# sensors_in.net
KiCad netlist of a schematic drawn in Altium Designer
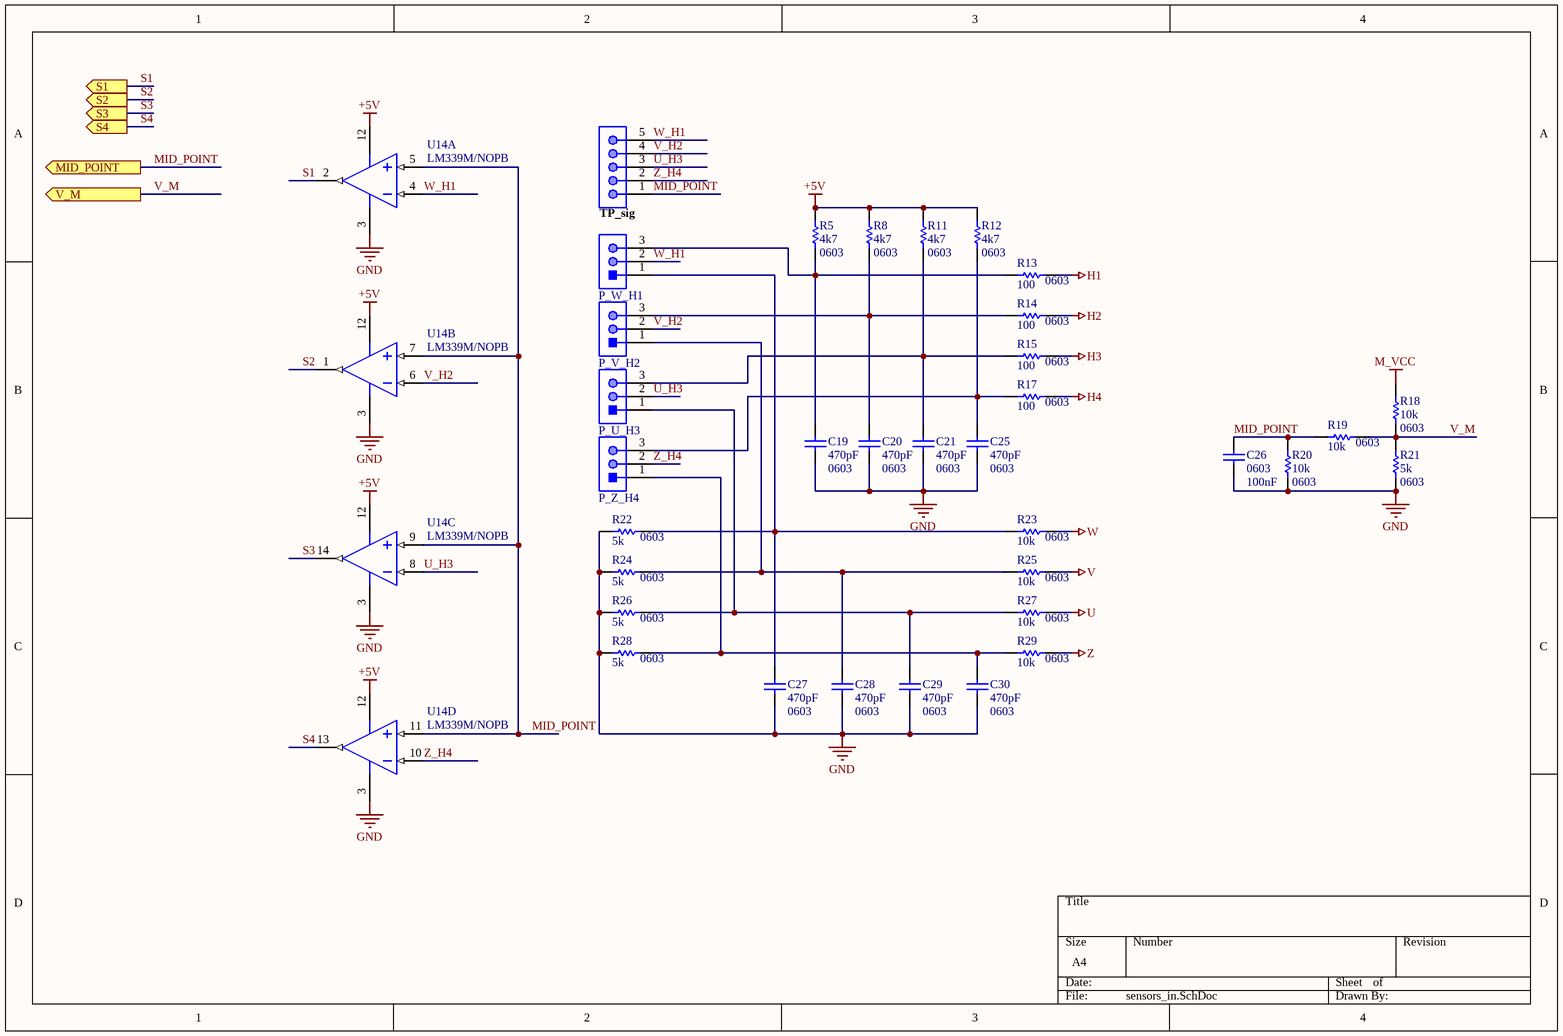
[diagram p0: sensors_in.SchDoc]

(export (version "E")
  (design (tool "Eeschema 10.0.6"))
  (components
    (comp (ref "C19")
      (value "470pF")
      (footprint "CAPC0603(1608)100_M")
      (description "CAP 470pF 25V ±5% 0603 (1608 Metric) Thickness 1mm SMD")
      (fields
        (field (name "TOLERANCE") "Â±5%")
        (field (name "CASE-EIA") "0603")
        (field (name "Comment") "CAP 470pF 25V 0603(1608)")
      )
      (libsource (lib "Altium Content Vault") (part "CAP"))
    )
    (comp (ref "C20")
      (value "470pF")
      (footprint "CAPC0603(1608)100_M")
      (description "CAP 470pF 25V ±5% 0603 (1608 Metric) Thickness 1mm SMD")
      (fields
        (field (name "TOLERANCE") "Â±5%")
        (field (name "CASE-EIA") "0603")
        (field (name "Comment") "CAP 470pF 25V 0603(1608)")
      )
      (libsource (lib "Altium Content Vault") (part "CAP"))
    )
    (comp (ref "C21")
      (value "470pF")
      (footprint "CAPC0603(1608)100_M")
      (description "CAP 470pF 25V ±5% 0603 (1608 Metric) Thickness 1mm SMD")
      (fields
        (field (name "TOLERANCE") "Â±5%")
        (field (name "CASE-EIA") "0603")
        (field (name "Comment") "CAP 470pF 25V 0603(1608)")
      )
      (libsource (lib "Altium Content Vault") (part "CAP"))
    )
    (comp (ref "C25")
      (value "470pF")
      (footprint "CAPC0603(1608)100_M")
      (description "CAP 470pF 25V ±5% 0603 (1608 Metric) Thickness 1mm SMD")
      (fields
        (field (name "TOLERANCE") "Â±5%")
        (field (name "CASE-EIA") "0603")
        (field (name "Comment") "CAP 470pF 25V 0603(1608)")
      )
      (libsource (lib "Altium Content Vault") (part "CAP"))
    )
    (comp (ref "C26")
      (value "GRM188R71H104KA93D")
      (footprint "CAPC1608X90X35ML10T15")
      (description "Chip Capacitor, 0.1 uF, +/- 10%, 50 V, -55 to 125 degC, 0603 (1608 Metric), RoHS, Tape and Reel")
      (fields
        (field (name "TOLERANCE") "10%")
        (field (name "CASE CODE (IMPERIAL)") "0603")
        (field (name "CAPACITANCE") "100nF")
        (field (name "VOLTAGE") "50V")
      )
      (libsource (lib "Altium Content Vault") (part "CAP-NP-2"))
    )
    (comp (ref "C27")
      (value "470pF")
      (footprint "CAPC0603(1608)100_M")
      (description "CAP 470pF 25V ±5% 0603 (1608 Metric) Thickness 1mm SMD")
      (fields
        (field (name "TOLERANCE") "Â±5%")
        (field (name "CASE-EIA") "0603")
        (field (name "Comment") "CAP 470pF 25V 0603(1608)")
      )
      (libsource (lib "Altium Content Vault") (part "CAP"))
    )
    (comp (ref "C28")
      (value "470pF")
      (footprint "CAPC0603(1608)100_M")
      (description "CAP 470pF 25V ±5% 0603 (1608 Metric) Thickness 1mm SMD")
      (fields
        (field (name "TOLERANCE") "Â±5%")
        (field (name "CASE-EIA") "0603")
        (field (name "Comment") "CAP 470pF 25V 0603(1608)")
      )
      (libsource (lib "Altium Content Vault") (part "CAP"))
    )
    (comp (ref "C29")
      (value "470pF")
      (footprint "CAPC0603(1608)100_M")
      (description "CAP 470pF 25V ±5% 0603 (1608 Metric) Thickness 1mm SMD")
      (fields
        (field (name "TOLERANCE") "Â±5%")
        (field (name "CASE-EIA") "0603")
        (field (name "Comment") "CAP 470pF 25V 0603(1608)")
      )
      (libsource (lib "Altium Content Vault") (part "CAP"))
    )
    (comp (ref "C30")
      (value "470pF")
      (footprint "CAPC0603(1608)100_M")
      (description "CAP 470pF 25V ±5% 0603 (1608 Metric) Thickness 1mm SMD")
      (fields
        (field (name "TOLERANCE") "Â±5%")
        (field (name "CASE-EIA") "0603")
        (field (name "Comment") "CAP 470pF 25V 0603(1608)")
      )
      (libsource (lib "Altium Content Vault") (part "CAP"))
    )
    (comp (ref "P_U_H3")
      (value "61300311121")
      (footprint "61300311121")
      (description "THT Vertical Pin Header WR-PHD, Pitch 2.54 mm, Single Row, 3 pins")
      (fields (field (name "MANUFACTURER") "Wurth Elektronik") (field (name "PUBLISHER") "WurthElektronik"))
      (libsource (lib "Altium Content Vault") (part "WE-CN-1P-M-R3"))
    )
    (comp (ref "P_V_H2")
      (value "61300311121")
      (footprint "61300311121")
      (description "THT Vertical Pin Header WR-PHD, Pitch 2.54 mm, Single Row, 3 pins")
      (fields (field (name "MANUFACTURER") "Wurth Elektronik") (field (name "PUBLISHER") "WurthElektronik"))
      (libsource (lib "Altium Content Vault") (part "WE-CN-1P-M-R3"))
    )
    (comp (ref "P_W_H1")
      (value "61300311121")
      (footprint "61300311121")
      (description "THT Vertical Pin Header WR-PHD, Pitch 2.54 mm, Single Row, 3 pins")
      (fields (field (name "MANUFACTURER") "Wurth Elektronik") (field (name "PUBLISHER") "WurthElektronik"))
      (libsource (lib "Altium Content Vault") (part "WE-CN-1P-M-R3"))
    )
    (comp (ref "P_Z_H4")
      (value "61300311121")
      (footprint "61300311121")
      (description "THT Vertical Pin Header WR-PHD, Pitch 2.54 mm, Single Row, 3 pins")
      (fields (field (name "MANUFACTURER") "Wurth Elektronik") (field (name "PUBLISHER") "WurthElektronik"))
      (libsource (lib "Altium Content Vault") (part "WE-CN-1P-M-R3"))
    )
    (comp (ref "R5")
      (value "RMCF0603FT10K0")
      (footprint "RESC1608X55X30ML15T20")
      (description "Chip Resistor, 10 KOhm, +/- 1%, 0.1 W, -55 to 155 degC, 0603 (1608 Metric), RoHS, Tape and Reel")
      (fields
        (field (name "RESISTANCE (OHMS)") "4k7")
        (field (name "TOLERANCE") "±1%")
        (field (name "PACKAGE REFERENCE") "0603")
        (field (name "MANUFACTURER") "Stackpole-Electronics-Inc.")
      )
      (libsource (lib "Altium Content Vault") (part "RES-2"))
    )
    (comp (ref "R8")
      (value "RMCF0603FT10K0")
      (footprint "RESC1608X55X30ML15T20")
      (description "Chip Resistor, 10 KOhm, +/- 1%, 0.1 W, -55 to 155 degC, 0603 (1608 Metric), RoHS, Tape and Reel")
      (fields
        (field (name "RESISTANCE (OHMS)") "4k7")
        (field (name "TOLERANCE") "±1%")
        (field (name "PACKAGE REFERENCE") "0603")
        (field (name "MANUFACTURER") "Stackpole-Electronics-Inc.")
      )
      (libsource (lib "Altium Content Vault") (part "RES-2"))
    )
    (comp (ref "R11")
      (value "RMCF0603FT10K0")
      (footprint "RESC1608X55X30ML15T20")
      (description "Chip Resistor, 10 KOhm, +/- 1%, 0.1 W, -55 to 155 degC, 0603 (1608 Metric), RoHS, Tape and Reel")
      (fields
        (field (name "RESISTANCE (OHMS)") "4k7")
        (field (name "TOLERANCE") "±1%")
        (field (name "PACKAGE REFERENCE") "0603")
        (field (name "MANUFACTURER") "Stackpole-Electronics-Inc.")
      )
      (libsource (lib "Altium Content Vault") (part "RES-2"))
    )
    (comp (ref "R12")
      (value "RMCF0603FT10K0")
      (footprint "RESC1608X55X30ML15T20")
      (description "Chip Resistor, 10 KOhm, +/- 1%, 0.1 W, -55 to 155 degC, 0603 (1608 Metric), RoHS, Tape and Reel")
      (fields
        (field (name "RESISTANCE (OHMS)") "4k7")
        (field (name "TOLERANCE") "±1%")
        (field (name "PACKAGE REFERENCE") "0603")
        (field (name "MANUFACTURER") "Stackpole-Electronics-Inc.")
      )
      (libsource (lib "Altium Content Vault") (part "RES-2"))
    )
    (comp (ref "R13")
      (value "RMCF0603FT10K0")
      (footprint "RESC1608X55X30ML15T20")
      (description "Chip Resistor, 10 KOhm, +/- 1%, 0.1 W, -55 to 155 degC, 0603 (1608 Metric), RoHS, Tape and Reel")
      (fields
        (field (name "RESISTANCE (OHMS)") "100")
        (field (name "TOLERANCE") "±1%")
        (field (name "PACKAGE REFERENCE") "0603")
        (field (name "MANUFACTURER") "Stackpole-Electronics-Inc.")
      )
      (libsource (lib "Altium Content Vault") (part "RES-2"))
    )
    (comp (ref "R14")
      (value "RMCF0603FT10K0")
      (footprint "RESC1608X55X30ML15T20")
      (description "Chip Resistor, 10 KOhm, +/- 1%, 0.1 W, -55 to 155 degC, 0603 (1608 Metric), RoHS, Tape and Reel")
      (fields
        (field (name "RESISTANCE (OHMS)") "100")
        (field (name "TOLERANCE") "±1%")
        (field (name "PACKAGE REFERENCE") "0603")
        (field (name "MANUFACTURER") "Stackpole-Electronics-Inc.")
      )
      (libsource (lib "Altium Content Vault") (part "RES-2"))
    )
    (comp (ref "R15")
      (value "RMCF0603FT10K0")
      (footprint "RESC1608X55X30ML15T20")
      (description "Chip Resistor, 10 KOhm, +/- 1%, 0.1 W, -55 to 155 degC, 0603 (1608 Metric), RoHS, Tape and Reel")
      (fields
        (field (name "RESISTANCE (OHMS)") "100")
        (field (name "TOLERANCE") "±1%")
        (field (name "PACKAGE REFERENCE") "0603")
        (field (name "MANUFACTURER") "Stackpole-Electronics-Inc.")
      )
      (libsource (lib "Altium Content Vault") (part "RES-2"))
    )
    (comp (ref "R17")
      (value "RMCF0603FT10K0")
      (footprint "RESC1608X55X30ML15T20")
      (description "Chip Resistor, 10 KOhm, +/- 1%, 0.1 W, -55 to 155 degC, 0603 (1608 Metric), RoHS, Tape and Reel")
      (fields
        (field (name "RESISTANCE (OHMS)") "100")
        (field (name "TOLERANCE") "±1%")
        (field (name "PACKAGE REFERENCE") "0603")
        (field (name "MANUFACTURER") "Stackpole-Electronics-Inc.")
      )
      (libsource (lib "Altium Content Vault") (part "RES-2"))
    )
    (comp (ref "R18")
      (value "RMCF0603FT10K0")
      (footprint "RESC1608X55X30ML15T20")
      (description "Chip Resistor, 10 KOhm, +/- 1%, 0.1 W, -55 to 155 degC, 0603 (1608 Metric), RoHS, Tape and Reel")
      (fields
        (field (name "RESISTANCE (OHMS)") "10k")
        (field (name "TOLERANCE") "±1%")
        (field (name "PACKAGE REFERENCE") "0603")
        (field (name "MANUFACTURER") "Stackpole-Electronics-Inc.")
      )
      (libsource (lib "Altium Content Vault") (part "RES-2"))
    )
    (comp (ref "R19")
      (value "RMCF0603FT10K0")
      (footprint "RESC1608X55X30ML15T20")
      (description "Chip Resistor, 10 KOhm, +/- 1%, 0.1 W, -55 to 155 degC, 0603 (1608 Metric), RoHS, Tape and Reel")
      (fields
        (field (name "RESISTANCE (OHMS)") "10k")
        (field (name "TOLERANCE") "±1%")
        (field (name "PACKAGE REFERENCE") "0603")
        (field (name "MANUFACTURER") "Stackpole-Electronics-Inc.")
      )
      (libsource (lib "Altium Content Vault") (part "RES-2"))
    )
    (comp (ref "R20")
      (value "RMCF0603FT10K0")
      (footprint "RESC1608X55X30ML15T20")
      (description "Chip Resistor, 10 KOhm, +/- 1%, 0.1 W, -55 to 155 degC, 0603 (1608 Metric), RoHS, Tape and Reel")
      (fields
        (field (name "RESISTANCE (OHMS)") "10k")
        (field (name "TOLERANCE") "±1%")
        (field (name "PACKAGE REFERENCE") "0603")
        (field (name "MANUFACTURER") "Stackpole-Electronics-Inc.")
      )
      (libsource (lib "Altium Content Vault") (part "RES-2"))
    )
    (comp (ref "R21")
      (value "RMCF0603FT10K0")
      (footprint "RESC1608X55X30ML15T20")
      (description "Chip Resistor, 10 KOhm, +/- 1%, 0.1 W, -55 to 155 degC, 0603 (1608 Metric), RoHS, Tape and Reel")
      (fields
        (field (name "RESISTANCE (OHMS)") "5k")
        (field (name "TOLERANCE") "±1%")
        (field (name "PACKAGE REFERENCE") "0603")
        (field (name "MANUFACTURER") "Stackpole-Electronics-Inc.")
      )
      (libsource (lib "Altium Content Vault") (part "RES-2"))
    )
    (comp (ref "R22")
      (value "RMCF0603FT10K0")
      (footprint "RESC1608X55X30ML15T20")
      (description "Chip Resistor, 10 KOhm, +/- 1%, 0.1 W, -55 to 155 degC, 0603 (1608 Metric), RoHS, Tape and Reel")
      (fields
        (field (name "RESISTANCE (OHMS)") "5k")
        (field (name "TOLERANCE") "±1%")
        (field (name "PACKAGE REFERENCE") "0603")
        (field (name "MANUFACTURER") "Stackpole-Electronics-Inc.")
      )
      (libsource (lib "Altium Content Vault") (part "RES-2"))
    )
    (comp (ref "R23")
      (value "RMCF0603FT10K0")
      (footprint "RESC1608X55X30ML15T20")
      (description "Chip Resistor, 10 KOhm, +/- 1%, 0.1 W, -55 to 155 degC, 0603 (1608 Metric), RoHS, Tape and Reel")
      (fields
        (field (name "RESISTANCE (OHMS)") "10k")
        (field (name "TOLERANCE") "±1%")
        (field (name "PACKAGE REFERENCE") "0603")
        (field (name "MANUFACTURER") "Stackpole-Electronics-Inc.")
      )
      (libsource (lib "Altium Content Vault") (part "RES-2"))
    )
    (comp (ref "R24")
      (value "RMCF0603FT10K0")
      (footprint "RESC1608X55X30ML15T20")
      (description "Chip Resistor, 10 KOhm, +/- 1%, 0.1 W, -55 to 155 degC, 0603 (1608 Metric), RoHS, Tape and Reel")
      (fields
        (field (name "RESISTANCE (OHMS)") "5k")
        (field (name "TOLERANCE") "±1%")
        (field (name "PACKAGE REFERENCE") "0603")
        (field (name "MANUFACTURER") "Stackpole-Electronics-Inc.")
      )
      (libsource (lib "Altium Content Vault") (part "RES-2"))
    )
    (comp (ref "R25")
      (value "RMCF0603FT10K0")
      (footprint "RESC1608X55X30ML15T20")
      (description "Chip Resistor, 10 KOhm, +/- 1%, 0.1 W, -55 to 155 degC, 0603 (1608 Metric), RoHS, Tape and Reel")
      (fields
        (field (name "RESISTANCE (OHMS)") "10k")
        (field (name "TOLERANCE") "±1%")
        (field (name "PACKAGE REFERENCE") "0603")
        (field (name "MANUFACTURER") "Stackpole-Electronics-Inc.")
      )
      (libsource (lib "Altium Content Vault") (part "RES-2"))
    )
    (comp (ref "R26")
      (value "RMCF0603FT10K0")
      (footprint "RESC1608X55X30ML15T20")
      (description "Chip Resistor, 10 KOhm, +/- 1%, 0.1 W, -55 to 155 degC, 0603 (1608 Metric), RoHS, Tape and Reel")
      (fields
        (field (name "RESISTANCE (OHMS)") "5k")
        (field (name "TOLERANCE") "±1%")
        (field (name "PACKAGE REFERENCE") "0603")
        (field (name "MANUFACTURER") "Stackpole-Electronics-Inc.")
      )
      (libsource (lib "Altium Content Vault") (part "RES-2"))
    )
    (comp (ref "R27")
      (value "RMCF0603FT10K0")
      (footprint "RESC1608X55X30ML15T20")
      (description "Chip Resistor, 10 KOhm, +/- 1%, 0.1 W, -55 to 155 degC, 0603 (1608 Metric), RoHS, Tape and Reel")
      (fields
        (field (name "RESISTANCE (OHMS)") "10k")
        (field (name "TOLERANCE") "±1%")
        (field (name "PACKAGE REFERENCE") "0603")
        (field (name "MANUFACTURER") "Stackpole-Electronics-Inc.")
      )
      (libsource (lib "Altium Content Vault") (part "RES-2"))
    )
    (comp (ref "R28")
      (value "RMCF0603FT10K0")
      (footprint "RESC1608X55X30ML15T20")
      (description "Chip Resistor, 10 KOhm, +/- 1%, 0.1 W, -55 to 155 degC, 0603 (1608 Metric), RoHS, Tape and Reel")
      (fields
        (field (name "RESISTANCE (OHMS)") "5k")
        (field (name "TOLERANCE") "±1%")
        (field (name "PACKAGE REFERENCE") "0603")
        (field (name "MANUFACTURER") "Stackpole-Electronics-Inc.")
      )
      (libsource (lib "Altium Content Vault") (part "RES-2"))
    )
    (comp (ref "R29")
      (value "RMCF0603FT10K0")
      (footprint "RESC1608X55X30ML15T20")
      (description "Chip Resistor, 10 KOhm, +/- 1%, 0.1 W, -55 to 155 degC, 0603 (1608 Metric), RoHS, Tape and Reel")
      (fields
        (field (name "RESISTANCE (OHMS)") "10k")
        (field (name "TOLERANCE") "±1%")
        (field (name "PACKAGE REFERENCE") "0603")
        (field (name "MANUFACTURER") "Stackpole-Electronics-Inc.")
      )
      (libsource (lib "Altium Content Vault") (part "RES-2"))
    )
    (comp (ref "TP_sig")
      (value "PH2541-5-SPGRH-6-3")
      (footprint "PH2541-5-SPGRH-6-3_V")
      (description "Male Header, Pitch 2.54mm, 5x1 Position, Mated Height 6mm, Tail Length 3mm")
      (libsource (lib "Altium Content Vault") (part "PCE-HDR-1P-M-R5"))
    )
    (comp (ref "U14")
      (value "LM339M/NOPB")
      (footprint "D0014A_L")
      (description "Low Power Low Offset Voltage Quad Comparator, 14-pin Narrow SOIC, Pb-Free")
      (fields (field (name "MANUFACTURER") "Texas Instruments"))
      (libsource (lib "Altium Content Vault") (part "AN-COMP-LM139-14"))
    )
  )
  (nets
    (net (code "1") (name "+5V") (class "Default")
      (node (ref "R11") (pin "2") (pinfunction "2_2") (pintype "passive"))
      (node (ref "R12") (pin "2") (pinfunction "2_2") (pintype "passive"))
      (node (ref "R5") (pin "2") (pinfunction "2_2") (pintype "passive"))
      (node (ref "R8") (pin "2") (pinfunction "2_2") (pintype "passive"))
      (node (ref "U14") (pin "12") (pinfunction "GND_12") (pintype "power_in"))
    )
    (net (code "2") (name "/MID_POINT") (class "Default")
      (node (ref "C26") (pin "2") (pinfunction "2_2") (pintype "passive"))
      (node (ref "R19") (pin "1") (pinfunction "1_1") (pintype "passive"))
      (node (ref "R20") (pin "2") (pinfunction "2_2") (pintype "passive"))
      (node (ref "TP_sig") (pin "1") (pinfunction "1_1") (pintype "passive"))
      (node (ref "U14") (pin "11") (pinfunction "IN4+_11") (pintype "input"))
      (node (ref "U14") (pin "5") (pinfunction "IN1+_5") (pintype "input"))
      (node (ref "U14") (pin "7") (pinfunction "IN2+_7") (pintype "input"))
      (node (ref "U14") (pin "9") (pinfunction "IN3+_9") (pintype "input"))
    )
    (net (code "3") (name "/S1") (class "Default")
      (node (ref "U14") (pin "2") (pinfunction "OUT1_2") (pintype "output"))
    )
    (net (code "4") (name "/S2") (class "Default")
      (node (ref "U14") (pin "1") (pinfunction "OUT2_1") (pintype "output"))
    )
    (net (code "5") (name "/S3") (class "Default")
      (node (ref "U14") (pin "14") (pinfunction "OUT3_14") (pintype "output"))
    )
    (net (code "6") (name "/S4") (class "Default")
      (node (ref "U14") (pin "13") (pinfunction "OUT4_13") (pintype "output"))
    )
    (net (code "7") (name "/U_H3") (class "Default")
      (node (ref "P_U_H3") (pin "2") (pinfunction "2_2") (pintype "passive"))
      (node (ref "TP_sig") (pin "3") (pinfunction "3_3") (pintype "passive"))
      (node (ref "U14") (pin "8") (pinfunction "IN3-_8") (pintype "input"))
    )
    (net (code "8") (name "/V_H2") (class "Default")
      (node (ref "P_V_H2") (pin "2") (pinfunction "2_2") (pintype "passive"))
      (node (ref "TP_sig") (pin "4") (pinfunction "4_4") (pintype "passive"))
      (node (ref "U14") (pin "6") (pinfunction "IN2-_6") (pintype "input"))
    )
    (net (code "9") (name "/V_M") (class "Default")
      (node (ref "R18") (pin "1") (pinfunction "1_1") (pintype "passive"))
      (node (ref "R19") (pin "2") (pinfunction "2_2") (pintype "passive"))
      (node (ref "R21") (pin "2") (pinfunction "2_2") (pintype "passive"))
    )
    (net (code "10") (name "/W_H1") (class "Default")
      (node (ref "P_W_H1") (pin "2") (pinfunction "2_2") (pintype "passive"))
      (node (ref "TP_sig") (pin "5") (pinfunction "5_5") (pintype "passive"))
      (node (ref "U14") (pin "4") (pinfunction "IN1-_4") (pintype "input"))
    )
    (net (code "11") (name "/Z_H4") (class "Default")
      (node (ref "P_Z_H4") (pin "2") (pinfunction "2_2") (pintype "passive"))
      (node (ref "TP_sig") (pin "2") (pinfunction "2_2") (pintype "passive"))
      (node (ref "U14") (pin "10") (pinfunction "IN4-_10") (pintype "input"))
    )
    (net (code "12") (name "GND") (class "Default")
      (node (ref "C19") (pin "1") (pinfunction "1_1") (pintype "passive"))
      (node (ref "C20") (pin "1") (pinfunction "1_1") (pintype "passive"))
      (node (ref "C21") (pin "1") (pinfunction "1_1") (pintype "passive"))
      (node (ref "C25") (pin "1") (pinfunction "1_1") (pintype "passive"))
      (node (ref "C26") (pin "1") (pinfunction "1_1") (pintype "passive"))
      (node (ref "C27") (pin "1") (pinfunction "1_1") (pintype "passive"))
      (node (ref "C28") (pin "1") (pinfunction "1_1") (pintype "passive"))
      (node (ref "C29") (pin "1") (pinfunction "1_1") (pintype "passive"))
      (node (ref "C30") (pin "1") (pinfunction "1_1") (pintype "passive"))
      (node (ref "R20") (pin "1") (pinfunction "1_1") (pintype "passive"))
      (node (ref "R21") (pin "1") (pinfunction "1_1") (pintype "passive"))
      (node (ref "R22") (pin "1") (pinfunction "1_1") (pintype "passive"))
      (node (ref "R24") (pin "1") (pinfunction "1_1") (pintype "passive"))
      (node (ref "R26") (pin "1") (pinfunction "1_1") (pintype "passive"))
      (node (ref "R28") (pin "1") (pinfunction "1_1") (pintype "passive"))
      (node (ref "U14") (pin "3") (pinfunction "V+_3") (pintype "power_in"))
    )
    (net (code "13") (name "H1") (class "Default")
      (node (ref "R13") (pin "2") (pinfunction "2_2") (pintype "passive"))
    )
    (net (code "14") (name "H2") (class "Default")
      (node (ref "R14") (pin "2") (pinfunction "2_2") (pintype "passive"))
    )
    (net (code "15") (name "H3") (class "Default")
      (node (ref "R15") (pin "2") (pinfunction "2_2") (pintype "passive"))
    )
    (net (code "16") (name "H4") (class "Default")
      (node (ref "R17") (pin "2") (pinfunction "2_2") (pintype "passive"))
    )
    (net (code "17") (name "M_VCC") (class "Default")
      (node (ref "R18") (pin "2") (pinfunction "2_2") (pintype "passive"))
    )
    (net (code "18") (name "Net-(C19-Pad2)") (class "Default")
      (node (ref "C19") (pin "2") (pinfunction "2_2") (pintype "passive"))
      (node (ref "P_W_H1") (pin "3") (pinfunction "3_3") (pintype "passive"))
      (node (ref "R13") (pin "1") (pinfunction "1_1") (pintype "passive"))
      (node (ref "R5") (pin "1") (pinfunction "1_1") (pintype "passive"))
    )
    (net (code "19") (name "Net-(C20-Pad2)") (class "Default")
      (node (ref "C20") (pin "2") (pinfunction "2_2") (pintype "passive"))
      (node (ref "P_V_H2") (pin "3") (pinfunction "3_3") (pintype "passive"))
      (node (ref "R14") (pin "1") (pinfunction "1_1") (pintype "passive"))
      (node (ref "R8") (pin "1") (pinfunction "1_1") (pintype "passive"))
    )
    (net (code "20") (name "Net-(C21-Pad2)") (class "Default")
      (node (ref "C21") (pin "2") (pinfunction "2_2") (pintype "passive"))
      (node (ref "P_U_H3") (pin "3") (pinfunction "3_3") (pintype "passive"))
      (node (ref "R11") (pin "1") (pinfunction "1_1") (pintype "passive"))
      (node (ref "R15") (pin "1") (pinfunction "1_1") (pintype "passive"))
    )
    (net (code "21") (name "Net-(C25-Pad2)") (class "Default")
      (node (ref "C25") (pin "2") (pinfunction "2_2") (pintype "passive"))
      (node (ref "P_Z_H4") (pin "3") (pinfunction "3_3") (pintype "passive"))
      (node (ref "R12") (pin "1") (pinfunction "1_1") (pintype "passive"))
      (node (ref "R17") (pin "1") (pinfunction "1_1") (pintype "passive"))
    )
    (net (code "22") (name "Net-(C27-Pad2)") (class "Default")
      (node (ref "C27") (pin "2") (pinfunction "2_2") (pintype "passive"))
      (node (ref "P_W_H1") (pin "1") (pinfunction "1_1") (pintype "passive"))
      (node (ref "R22") (pin "2") (pinfunction "2_2") (pintype "passive"))
      (node (ref "R23") (pin "1") (pinfunction "1_1") (pintype "passive"))
    )
    (net (code "23") (name "Net-(C28-Pad2)") (class "Default")
      (node (ref "C28") (pin "2") (pinfunction "2_2") (pintype "passive"))
      (node (ref "P_V_H2") (pin "1") (pinfunction "1_1") (pintype "passive"))
      (node (ref "R24") (pin "2") (pinfunction "2_2") (pintype "passive"))
      (node (ref "R25") (pin "1") (pinfunction "1_1") (pintype "passive"))
    )
    (net (code "24") (name "Net-(C29-Pad2)") (class "Default")
      (node (ref "C29") (pin "2") (pinfunction "2_2") (pintype "passive"))
      (node (ref "P_U_H3") (pin "1") (pinfunction "1_1") (pintype "passive"))
      (node (ref "R26") (pin "2") (pinfunction "2_2") (pintype "passive"))
      (node (ref "R27") (pin "1") (pinfunction "1_1") (pintype "passive"))
    )
    (net (code "25") (name "Net-(C30-Pad2)") (class "Default")
      (node (ref "C30") (pin "2") (pinfunction "2_2") (pintype "passive"))
      (node (ref "P_Z_H4") (pin "1") (pinfunction "1_1") (pintype "passive"))
      (node (ref "R28") (pin "2") (pinfunction "2_2") (pintype "passive"))
      (node (ref "R29") (pin "1") (pinfunction "1_1") (pintype "passive"))
    )
    (net (code "26") (name "U") (class "Default")
      (node (ref "R27") (pin "2") (pinfunction "2_2") (pintype "passive"))
    )
    (net (code "27") (name "V") (class "Default")
      (node (ref "R25") (pin "2") (pinfunction "2_2") (pintype "passive"))
    )
    (net (code "28") (name "W") (class "Default")
      (node (ref "R23") (pin "2") (pinfunction "2_2") (pintype "passive"))
    )
    (net (code "29") (name "Z") (class "Default")
      (node (ref "R29") (pin "2") (pinfunction "2_2") (pintype "passive"))
    )
  )
)
